# PCB.net
KiCad netlist of a schematic drawn in EAGLE
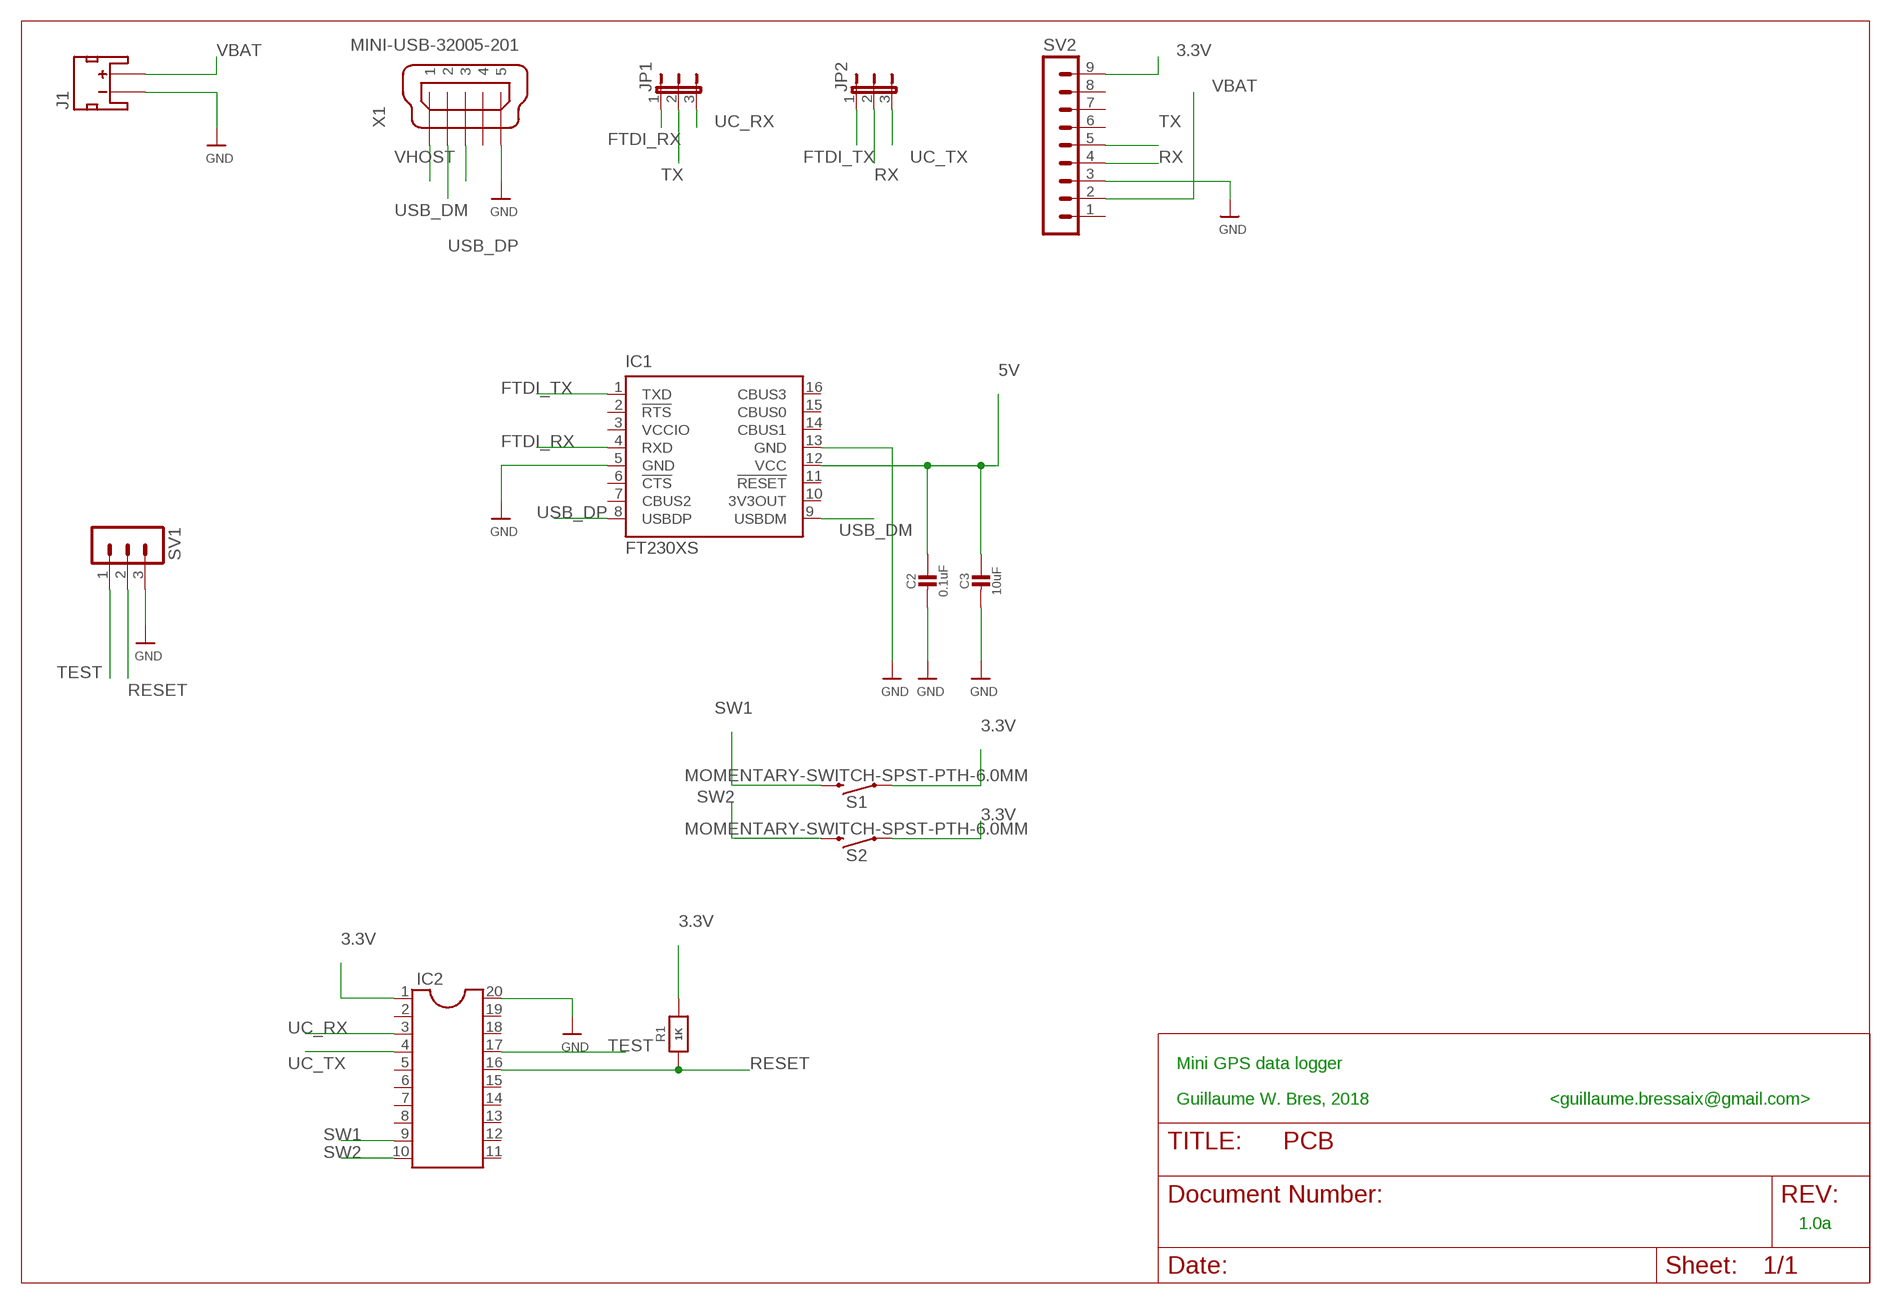
[diagram p0: schematic, sheet 1]

(export (version "E")
  (design (tool "Eeschema 10.0.6"))
  (components
    (comp (ref "C2")
      (value "0.1uF")
      (footprint "eagle-import:0805-NO")
      (libsource (lib "eagle-import") (part "CAP_CERAMIC0805-NOOUTLINE"))
    )
    (comp (ref "C3")
      (value "10uF")
      (footprint "eagle-import:0805-NO")
      (libsource (lib "eagle-import") (part "CAP_CERAMIC0805-NOOUTLINE"))
    )
    (comp (ref "IC1")
      (value "FT230XS")
      (footprint "eagle-import:SSOP16")
      (libsource (lib "eagle-import") (part "FT230XS"))
    )
    (comp (ref "IC2")
      (value "DIL20")
      (footprint "eagle-import:DIL20")
      (libsource (lib "eagle-import") (part "DIL20"))
    )
    (comp (ref "J1")
      (value "JST_2MM_MALE")
      (footprint "eagle-import:JST-2-SMD")
      (libsource (lib "eagle-import") (part "JST_2MM_MALE"))
    )
    (comp (ref "JP1")
      (value "JP2E")
      (footprint "eagle-import:JP2")
      (libsource (lib "eagle-import") (part "JP2E"))
    )
    (comp (ref "JP2")
      (value "JP2E")
      (footprint "eagle-import:JP2")
      (libsource (lib "eagle-import") (part "JP2E"))
    )
    (comp (ref "R1")
      (value "1K")
      (footprint "eagle-import:0805-NO")
      (libsource (lib "eagle-import") (part "RESISTOR0805_NOOUTLINE"))
    )
    (comp (ref "S1")
      (value "MOMENTARY-SWITCH-SPST-PTH-6.0MM")
      (footprint "eagle-import:TACTILE_SWITCH_PTH_6.0MM")
      (libsource (lib "eagle-import") (part "MOMENTARY-SWITCH-SPST-PTH-6.0MM"))
    )
    (comp (ref "S2")
      (value "MOMENTARY-SWITCH-SPST-PTH-6.0MM")
      (footprint "eagle-import:TACTILE_SWITCH_PTH_6.0MM")
      (libsource (lib "eagle-import") (part "MOMENTARY-SWITCH-SPST-PTH-6.0MM"))
    )
    (comp (ref "SV1")
      (value "MA03-1")
      (footprint "eagle-import:MA03-1")
      (libsource (lib "eagle-import") (part "MA03-1"))
    )
    (comp (ref "SV2")
      (value "MA09-1")
      (footprint "eagle-import:MA09-1")
      (libsource (lib "eagle-import") (part "MA09-1"))
    )
    (comp (ref "X1")
      (value "MINI-USB-32005-201")
      (footprint "eagle-import:32005-201")
      (libsource (lib "eagle-import") (part "MINI-USB-32005-201"))
    )
  )
  (nets
    (net (code "1") (name "/3.3V") (class "Default")
      (node (ref "IC2") (pin "1") (pinfunction "1_1") (pintype "passive"))
      (node (ref "R1") (pin "2") (pinfunction "2_2") (pintype "passive"))
      (node (ref "S1") (pin "1") (pinfunction "1_1") (pintype "passive"))
      (node (ref "S2") (pin "1") (pinfunction "1_1") (pintype "passive"))
      (node (ref "SV2") (pin "9") (pinfunction "9_9") (pintype "passive"))
    )
    (net (code "2") (name "/5V") (class "Default")
      (node (ref "C2") (pin "1") (pinfunction "1_1") (pintype "passive"))
      (node (ref "C3") (pin "1") (pinfunction "1_1") (pintype "passive"))
      (node (ref "IC1") (pin "12") (pinfunction "VCC_12") (pintype "power_in"))
    )
    (net (code "3") (name "/FTDI_RX") (class "Default")
      (node (ref "IC1") (pin "4") (pinfunction "RXD_4") (pintype "input"))
      (node (ref "JP1") (pin "1") (pinfunction "1_1") (pintype "passive"))
    )
    (net (code "4") (name "/FTDI_TX") (class "Default")
      (node (ref "IC1") (pin "1") (pinfunction "TXD_1") (pintype "output"))
      (node (ref "JP2") (pin "1") (pinfunction "1_1") (pintype "passive"))
    )
    (net (code "5") (name "/RESET") (class "Default")
      (node (ref "IC2") (pin "16") (pinfunction "16_16") (pintype "passive"))
      (node (ref "R1") (pin "1") (pinfunction "1_1") (pintype "passive"))
      (node (ref "SV1") (pin "2") (pinfunction "2_2") (pintype "passive"))
    )
    (net (code "6") (name "/RX") (class "Default")
      (node (ref "JP2") (pin "2") (pinfunction "2_2") (pintype "passive"))
      (node (ref "SV2") (pin "4") (pinfunction "4_4") (pintype "passive"))
    )
    (net (code "7") (name "/SW1") (class "Default")
      (node (ref "IC2") (pin "9") (pinfunction "9_9") (pintype "passive"))
      (node (ref "S1") (pin "3") (pinfunction "2_3") (pintype "passive"))
    )
    (net (code "8") (name "/SW2") (class "Default")
      (node (ref "IC2") (pin "10") (pinfunction "10_10") (pintype "passive"))
      (node (ref "S2") (pin "3") (pinfunction "2_3") (pintype "passive"))
    )
    (net (code "9") (name "/TEST") (class "Default")
      (node (ref "IC2") (pin "17") (pinfunction "17_17") (pintype "passive"))
      (node (ref "SV1") (pin "1") (pinfunction "1_1") (pintype "passive"))
    )
    (net (code "10") (name "/TX") (class "Default")
      (node (ref "JP1") (pin "2") (pinfunction "2_2") (pintype "passive"))
      (node (ref "SV2") (pin "5") (pinfunction "5_5") (pintype "passive"))
    )
    (net (code "11") (name "/UC_RX") (class "Default")
      (node (ref "IC2") (pin "3") (pinfunction "3_3") (pintype "passive"))
      (node (ref "JP1") (pin "3") (pinfunction "3_3") (pintype "passive"))
    )
    (net (code "12") (name "/UC_TX") (class "Default")
      (node (ref "IC2") (pin "4") (pinfunction "4_4") (pintype "passive"))
      (node (ref "JP2") (pin "3") (pinfunction "3_3") (pintype "passive"))
    )
    (net (code "13") (name "/USB_DM") (class "Default")
      (node (ref "IC1") (pin "9") (pinfunction "USBDM_9") (pintype "input"))
      (node (ref "X1") (pin "2") (pinfunction "2_2") (pintype "passive"))
    )
    (net (code "14") (name "/USB_DP") (class "Default")
      (node (ref "IC1") (pin "8") (pinfunction "USBDP_8") (pintype "input"))
      (node (ref "X1") (pin "3") (pinfunction "3_3") (pintype "passive"))
    )
    (net (code "15") (name "/VBAT") (class "Default")
      (node (ref "J1") (pin "2") (pinfunction "+_2") (pintype "bidirectional"))
      (node (ref "SV2") (pin "2") (pinfunction "2_2") (pintype "passive"))
    )
    (net (code "16") (name "/VCCIO") (class "Default")
      (node (ref "IC1") (pin "3") (pinfunction "VCCIO_3") (pintype "power_in"))
    )
    (net (code "17") (name "/VHOST") (class "Default")
      (node (ref "X1") (pin "1") (pinfunction "1_1") (pintype "passive"))
    )
    (net (code "18") (name "GND") (class "Default")
      (node (ref "C2") (pin "2") (pinfunction "2_2") (pintype "passive"))
      (node (ref "C3") (pin "2") (pinfunction "2_2") (pintype "passive"))
      (node (ref "IC1") (pin "13") (pinfunction "GND_13") (pintype "power_in"))
      (node (ref "IC1") (pin "5") (pinfunction "GND_5") (pintype "power_in"))
      (node (ref "IC2") (pin "20") (pinfunction "20_20") (pintype "passive"))
      (node (ref "J1") (pin "1") (pinfunction "-_1") (pintype "bidirectional"))
      (node (ref "SV1") (pin "3") (pinfunction "3_3") (pintype "passive"))
      (node (ref "SV2") (pin "3") (pinfunction "3_3") (pintype "passive"))
      (node (ref "X1") (pin "5") (pinfunction "5_5") (pintype "passive"))
    )
    (net (code "19") (name "unconnected-(IC1-3V3OUT-Pad10)") (class "Default")
      (node (ref "IC1") (pin "10") (pinfunction "3V3OUT_10") (pintype "output"))
    )
    (net (code "20") (name "unconnected-(IC1-CBUS0-Pad15)") (class "Default")
      (node (ref "IC1") (pin "15") (pinfunction "CBUS0_15") (pintype "bidirectional"))
    )
    (net (code "21") (name "unconnected-(IC1-CBUS1-Pad14)") (class "Default")
      (node (ref "IC1") (pin "14") (pinfunction "CBUS1_14") (pintype "bidirectional"))
    )
    (net (code "22") (name "unconnected-(IC1-CBUS2-Pad7)") (class "Default")
      (node (ref "IC1") (pin "7") (pinfunction "CBUS2_7") (pintype "bidirectional"))
    )
    (net (code "23") (name "unconnected-(IC1-CBUS3-Pad16)") (class "Default")
      (node (ref "IC1") (pin "16") (pinfunction "CBUS3_16") (pintype "bidirectional"))
    )
    (net (code "24") (name "unconnected-(IC1-~{CTS}-Pad6)") (class "Default")
      (node (ref "IC1") (pin "6") (pinfunction "~{CTS}_6") (pintype "input"))
    )
    (net (code "25") (name "unconnected-(IC1-~{RESET}-Pad11)") (class "Default")
      (node (ref "IC1") (pin "11") (pinfunction "~{RESET}_11") (pintype "input"))
    )
    (net (code "26") (name "unconnected-(IC1-~{RTS}-Pad2)") (class "Default")
      (node (ref "IC1") (pin "2") (pinfunction "~{RTS}_2") (pintype "output"))
    )
    (net (code "27") (name "unconnected-(IC2-Pad2)") (class "Default")
      (node (ref "IC2") (pin "2") (pinfunction "2_2") (pintype "passive"))
    )
    (net (code "28") (name "unconnected-(IC2-Pad5)") (class "Default")
      (node (ref "IC2") (pin "5") (pinfunction "5_5") (pintype "passive"))
    )
    (net (code "29") (name "unconnected-(IC2-Pad6)") (class "Default")
      (node (ref "IC2") (pin "6") (pinfunction "6_6") (pintype "passive"))
    )
    (net (code "30") (name "unconnected-(IC2-Pad7)") (class "Default")
      (node (ref "IC2") (pin "7") (pinfunction "7_7") (pintype "passive"))
    )
    (net (code "31") (name "unconnected-(IC2-Pad8)") (class "Default")
      (node (ref "IC2") (pin "8") (pinfunction "8_8") (pintype "passive"))
    )
    (net (code "32") (name "unconnected-(IC2-Pad11)") (class "Default")
      (node (ref "IC2") (pin "11") (pinfunction "11_11") (pintype "passive"))
    )
    (net (code "33") (name "unconnected-(IC2-Pad12)") (class "Default")
      (node (ref "IC2") (pin "12") (pinfunction "12_12") (pintype "passive"))
    )
    (net (code "34") (name "unconnected-(IC2-Pad13)") (class "Default")
      (node (ref "IC2") (pin "13") (pinfunction "13_13") (pintype "passive"))
    )
    (net (code "35") (name "unconnected-(IC2-Pad14)") (class "Default")
      (node (ref "IC2") (pin "14") (pinfunction "14_14") (pintype "passive"))
    )
    (net (code "36") (name "unconnected-(IC2-Pad15)") (class "Default")
      (node (ref "IC2") (pin "15") (pinfunction "15_15") (pintype "passive"))
    )
    (net (code "37") (name "unconnected-(IC2-Pad18)") (class "Default")
      (node (ref "IC2") (pin "18") (pinfunction "18_18") (pintype "passive"))
    )
    (net (code "38") (name "unconnected-(IC2-Pad19)") (class "Default")
      (node (ref "IC2") (pin "19") (pinfunction "19_19") (pintype "passive"))
    )
    (net (code "39") (name "unconnected-(J1-PAD1-PadNC1)") (class "Default")
      (node (ref "J1") (pin "NC1") (pinfunction "PAD1_NC1") (pintype "bidirectional"))
    )
    (net (code "40") (name "unconnected-(J1-PAD2-PadNC2)") (class "Default")
      (node (ref "J1") (pin "NC2") (pinfunction "PAD2_NC2") (pintype "bidirectional"))
    )
    (net (code "41") (name "unconnected-(SV2-Pad1)") (class "Default")
      (node (ref "SV2") (pin "1") (pinfunction "1_1") (pintype "passive"))
    )
    (net (code "42") (name "unconnected-(SV2-Pad6)") (class "Default")
      (node (ref "SV2") (pin "6") (pinfunction "6_6") (pintype "passive"))
    )
    (net (code "43") (name "unconnected-(SV2-Pad7)") (class "Default")
      (node (ref "SV2") (pin "7") (pinfunction "7_7") (pintype "passive"))
    )
    (net (code "44") (name "unconnected-(SV2-Pad8)") (class "Default")
      (node (ref "SV2") (pin "8") (pinfunction "8_8") (pintype "passive"))
    )
    (net (code "45") (name "unconnected-(X1-Pad4)") (class "Default")
      (node (ref "X1") (pin "4") (pinfunction "4_4") (pintype "passive"))
    )
  )
)
